# Daughterboard_Power.net
KiCad netlist of a schematic drawn in Altium Designer
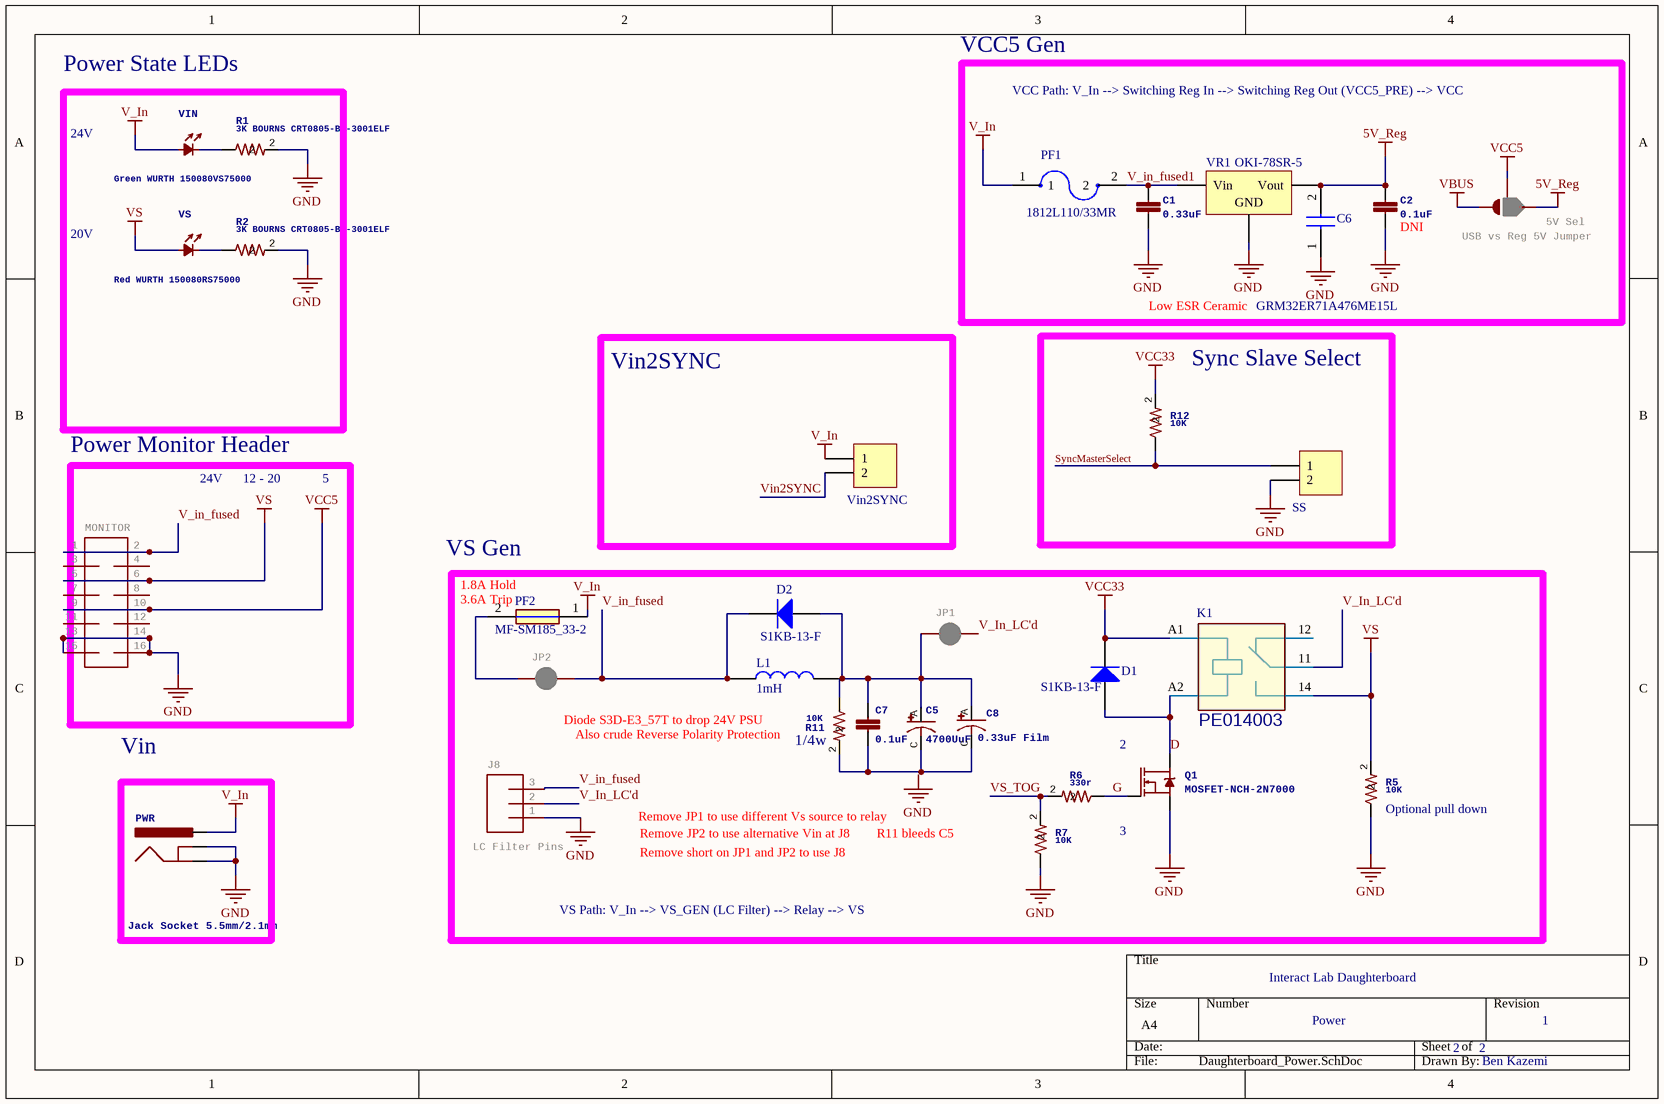
[diagram p0: Daughterboard_Power.SchDoc]

(export (version "E")
  (design (tool "Eeschema 10.0.6"))
  (components
    (comp (ref "5V Sel")
      (value "USB vs Reg 5V Jumper")
      (footprint "SMT-JUMPER_3_1-NC_PASTE_SILK")
      (libsource (lib "SparkFun-Jumpers.Library") (part "JUMPER-SMT_3_1-NC_PASTE_SILK"))
    )
    (comp (ref "C1")
      (value "0.33uF")
      (footprint "CAP0805")
      (libsource (lib "InteractLab") (part "CAP CERAMIC"))
    )
    (comp (ref "C2")
      (value "0.1uF")
      (footprint "CAP0805")
      (libsource (lib "InteractLab") (part "CAP CERAMIC"))
    )
    (comp (ref "C5")
      (value "4700UuF")
      (footprint "CAP-PTH-10MM PITCH 22M")
      (libsource (lib "InteractLab") (part "CAP ELECTRO"))
    )
    (comp (ref "C6")
      (value "GRM32ER71A476ME15L")
      (footprint "SamacSys:CAPC3225X270N")
      (description "Capacitor")
      (fields (field (name "MOUSER PART NUMBER") "81-GRM32ER71A476ME5L"))
      (libsource (lib "*") (part "GRM32ER71A476ME15L"))
    )
    (comp (ref "C7")
      (value "0.1uF")
      (footprint "CAP0805")
      (libsource (lib "InteractLab") (part "CAP CERAMIC"))
    )
    (comp (ref "C8")
      (value "0.33uF Film")
      (footprint "R82DC3330AA60K Film Cap")
      (libsource (lib "InteractLab") (part "CAP ELECTRO"))
    )
    (comp (ref "D1")
      (value "S1KB-13-F")
      (footprint "SMB-DIODE")
      (description "1 Amp General Purpose Rectifier")
      (fields (field (name "PUBLISHER") "Altium Limited"))
      (libsource (lib "InteractLab") (part "Diode SMB"))
    )
    (comp (ref "D2")
      (value "S1KB-13-F")
      (footprint "SMB-DIODE")
      (description "1 Amp General Purpose Rectifier")
      (fields (field (name "PUBLISHER") "Altium Limited"))
      (libsource (lib "InteractLab") (part "Diode SMB"))
    )
    (comp (ref "J8")
      (value "LC Filter Pins")
      (footprint "1X03")
      (libsource (lib "SparkFun-Connectors.Library") (part "CONN_03"))
    )
    (comp (ref "JP1")
      (value "~")
      (footprint "SMT-JUMPER_2_NC_PASTE_SILK")
      (libsource (lib "SparkFun-Jumpers.Library") (part "JUMPER-SMT_2_NC_PASTE_SILK"))
    )
    (comp (ref "JP2")
      (value "~")
      (footprint "SMT-JUMPER_2_NC_PASTE_SILK")
      (libsource (lib "SparkFun-Jumpers.Library") (part "JUMPER-SMT_2_NC_PASTE_SILK"))
    )
    (comp (ref "K1")
      (value "PE014003")
      (footprint "SPDT Power Relay")
      (fields (field (name "MP") "1-1393219-0") (field (name "MF") "TE Connectivity"))
      (libsource (lib "InteractLab") (part "Power Relay SPDT"))
    )
    (comp (ref "L1")
      (value "1mH")
      (footprint "INDUCTOR Hor 2324VRC")
      (description "Bourns 1 mH +/-15% Leaded Inductor, 2.4A Idc, 300m Rdc 2300")
      (fields (field (name "RS PART NUMBER") "1729913") (field (name "MANUFACTURER_PART_NUMBER") "2324-V-RC"))
      (libsource (lib "InteractLab") (part "INDUCTOR 2324-V-RC"))
    )
    (comp (ref "MONITOR")
      (value "Multi connection point. Often used as Generic Header-pin footprint for 0.1 inch spaced/style header connections    You can populate with any combo of single row headers, but if you'd like an exact match, check this:  Header - 2x8 (Male, 0.1\") (PRT-13156)       On any of the 0.1 inch spaced packages, you can populate with these:  Break Away Headers - Straight (PRT-00116)   Break Away Male Headers - Right Angle (PRT-00553)   Female Headers (PRT-00115)   Break Away Headers - Machine Pin (PRT-00117)   Break Away Female Headers - Swiss Machine Pin (PRT-00743)")
      (footprint "2X8_NOSILK")
      (libsource (lib "SparkFun-Connectors.Library") (part "CONN_08X2_NOSILK"))
    )
    (comp (ref "PF1")
      (value "1812L110/33MR")
      (footprint "Polyfuse")
      (description "PTC Resettable Fuse 1.1A_hold_ 1.95A_trip_ 33VDC 20A 0.8W 0.5s 0.06Ohm SMD Solder Pad 1812 T/R")
      (fields (field (name "MF") "Littelfuse Inc."))
      (libsource (lib "InteractLab") (part "1812L110/33MR"))
    )
    (comp (ref "PF2")
      (value "MF-SM185_33-2")
      (footprint "SamacSys:FUSM8867X300N")
      (description "Fuse")
      (fields
        (field (name "MANUFACTURER_PART_NUMBER") "MF-SM185/33-2")
        (field (name "MOUSER PART NUMBER") "652-MF-SM185/33-2")
      )
      (libsource (lib "*") (part "MF-SM185_33-2"))
    )
    (comp (ref "PWR")
      (value "Jack Socket 5.5mm/2.1mm")
      (footprint "POWER_JACK_PTH_LOCK")
      (libsource (lib "InteractLab") (part "POWER_JACKPTH_LOCK"))
    )
    (comp (ref "Q1")
      (value "MOSFET-NCH-2N7000")
      (footprint "TO-92")
      (libsource (lib "InteractLab") (part "MOSFET-NCH-2N7000"))
    )
    (comp (ref "R1")
      (value "3K BOURNS CRT0805-BY-3001ELF")
      (footprint "RES-0805")
      (fields (field (name "MF") "Vishay") (field (name "MPN") "CRCW0603470RFKEA"))
      (libsource (lib "InteractLab") (part "RESISTOR"))
    )
    (comp (ref "R2")
      (value "3K BOURNS CRT0805-BY-3001ELF")
      (footprint "RES-0805")
      (fields (field (name "MF") "Vishay") (field (name "MPN") "CRCW0603470RFKEA"))
      (libsource (lib "InteractLab") (part "RESISTOR"))
    )
    (comp (ref "R5")
      (value "10K")
      (footprint "RES-0805")
      (fields (field (name "MF") "Vishay") (field (name "MPN") "CRCW0603470RFKEA"))
      (libsource (lib "InteractLab") (part "RESISTOR"))
    )
    (comp (ref "R6")
      (value "330r")
      (footprint "RES-0805")
      (fields (field (name "MF") "Vishay") (field (name "MPN") "CRCW0603470RFKEA"))
      (libsource (lib "InteractLab") (part "RESISTOR"))
    )
    (comp (ref "R7")
      (value "10K")
      (footprint "RES-0805")
      (fields (field (name "MF") "Vishay") (field (name "MPN") "CRCW0603470RFKEA"))
      (libsource (lib "InteractLab") (part "RESISTOR"))
    )
    (comp (ref "R11")
      (value "10K")
      (footprint "RES-0805")
      (fields (field (name "MF") "Vishay") (field (name "MPN") "CRCW0603470RFKEA"))
      (libsource (lib "InteractLab") (part "RESISTOR"))
    )
    (comp (ref "R12")
      (value "10K")
      (footprint "RES-0805")
      (fields (field (name "MF") "Vishay") (field (name "MPN") "CRCW0603470RFKEA"))
      (libsource (lib "InteractLab") (part "RESISTOR"))
    )
    (comp (ref "SS")
      (value "~")
      (footprint "HDR1X2")
      (description "Header, 2-Pin")
      (fields (field (name "PUBLISHER") "Altium Limited"))
      (libsource (lib "Miscellaneous Connectors") (part "Header 2"))
    )
    (comp (ref "VIN")
      (value "Green WURTH 150080VS75000")
      (footprint "LED-0805 - GREEN")
      (libsource (lib "InteractLab") (part "LED"))
    )
    (comp (ref "Vin2SYNC")
      (value "~")
      (footprint "HDR1X2")
      (description "Header, 2-Pin")
      (fields (field (name "PUBLISHER") "Altium Limited"))
      (libsource (lib "Miscellaneous Connectors") (part "Header 2"))
    )
    (comp (ref "VR1")
      (value "OKI-78SR-5")
      (footprint "OOKA-78SR")
      (description "Voltage Regulator")
      (fields (field (name "PUBLISHER") "Altium Limited"))
      (libsource (lib "InteractLab") (part "Volt Reg"))
    )
    (comp (ref "VS")
      (value "Red WURTH 150080RS75000")
      (footprint "LED-0805 - RED")
      (libsource (lib "InteractLab") (part "LED"))
    )
  )
  (nets
    (net (code "1") (name "/D") (class "Default")
      (node (ref "D1") (pin "A") (pinfunction "A_A") (pintype "passive"))
      (node (ref "K1") (pin "A2") (pinfunction "A2_A2") (pintype "passive"))
      (node (ref "Q1") (pin "3") (pinfunction "D_3") (pintype "passive"))
    )
    (net (code "2") (name "/G") (class "Default")
      (node (ref "Q1") (pin "2") (pinfunction "G_2") (pintype "passive"))
      (node (ref "R6") (pin "1") (pinfunction "1_1") (pintype "passive"))
    )
    (net (code "3") (name "/SyncMasterSelect") (class "Default")
      (node (ref "R12") (pin "1") (pinfunction "1_1") (pintype "passive"))
      (node (ref "SS") (pin "1") (pinfunction "1_1") (pintype "passive"))
    )
    (net (code "4") (name "/VS_TOG") (class "Default")
      (node (ref "R6") (pin "2") (pinfunction "2_2") (pintype "passive"))
      (node (ref "R7") (pin "2") (pinfunction "2_2") (pintype "passive"))
    )
    (net (code "5") (name "/V_In_LC'd") (class "Default")
      (node (ref "J8") (pin "2") (pinfunction "2_2") (pintype "passive"))
      (node (ref "JP1") (pin "2") (pinfunction "2_2") (pintype "passive"))
      (node (ref "K1") (pin "11") (pinfunction "11_11") (pintype "passive"))
    )
    (net (code "6") (name "/V_in_fused") (class "Default")
      (node (ref "D2") (pin "C") (pinfunction "C_C") (pintype "passive"))
      (node (ref "J8") (pin "3") (pinfunction "3_3") (pintype "passive"))
      (node (ref "JP2") (pin "2") (pinfunction "2_2") (pintype "passive"))
      (node (ref "L1") (pin "1") (pinfunction "1_1") (pintype "passive"))
      (node (ref "MONITOR") (pin "1") (pinfunction "1_1") (pintype "passive"))
      (node (ref "MONITOR") (pin "2") (pinfunction "2_2") (pintype "passive"))
    )
    (net (code "7") (name "/V_in_fused1") (class "Default")
      (node (ref "C1") (pin "1") (pinfunction "1_1") (pintype "passive"))
      (node (ref "PF1") (pin "2") (pinfunction "2_2") (pintype "passive"))
      (node (ref "VR1") (pin "IN") (pinfunction "Vin_IN") (pintype "passive"))
    )
    (net (code "8") (name "/Vin2SYNC") (class "Default")
      (node (ref "Vin2SYNC") (pin "2") (pinfunction "2_2") (pintype "passive"))
    )
    (net (code "9") (name "5V_Reg") (class "Default")
      (node (ref "5V Sel") (pin "3") (pinfunction "3_3") (pintype "passive"))
      (node (ref "C2") (pin "1") (pinfunction "1_1") (pintype "passive"))
      (node (ref "C6") (pin "2") (pinfunction "2_2") (pintype "passive"))
      (node (ref "VR1") (pin "OUT") (pinfunction "Vout_OUT") (pintype "passive"))
    )
    (net (code "10") (name "GND") (class "Default")
      (node (ref "C1") (pin "2") (pinfunction "2_2") (pintype "passive"))
      (node (ref "C2") (pin "2") (pinfunction "2_2") (pintype "passive"))
      (node (ref "C6") (pin "1") (pinfunction "1_1") (pintype "passive"))
      (node (ref "J8") (pin "1") (pinfunction "1_1") (pintype "passive"))
      (node (ref "MONITOR") (pin "13") (pinfunction "13_13") (pintype "passive"))
      (node (ref "MONITOR") (pin "14") (pinfunction "14_14") (pintype "passive"))
      (node (ref "MONITOR") (pin "15") (pinfunction "15_15") (pintype "passive"))
      (node (ref "MONITOR") (pin "16") (pinfunction "16_16") (pintype "passive"))
      (node (ref "PWR") (pin "GND") (pinfunction "GND_GND") (pintype "passive"))
      (node (ref "PWR") (pin "GNDBREAK") (pinfunction "GNDBREAK_GNDBREAK") (pintype "passive"))
      (node (ref "Q1") (pin "1") (pinfunction "S_1") (pintype "passive"))
      (node (ref "R1") (pin "2") (pinfunction "2_2") (pintype "passive"))
      (node (ref "R2") (pin "2") (pinfunction "2_2") (pintype "passive"))
      (node (ref "R5") (pin "1") (pinfunction "1_1") (pintype "passive"))
      (node (ref "R7") (pin "1") (pinfunction "1_1") (pintype "passive"))
      (node (ref "SS") (pin "2") (pinfunction "2_2") (pintype "passive"))
      (node (ref "VR1") (pin "GND") (pinfunction "GND_GND") (pintype "passive"))
    )
    (net (code "11") (name "Net-(C5-PadA)") (class "Default")
      (node (ref "C5") (pin "A") (pinfunction "A_A") (pintype "passive"))
      (node (ref "C7") (pin "1") (pinfunction "1_1") (pintype "passive"))
      (node (ref "C8") (pin "A") (pinfunction "A_A") (pintype "passive"))
      (node (ref "D2") (pin "A") (pinfunction "A_A") (pintype "passive"))
      (node (ref "JP1") (pin "1") (pinfunction "1_1") (pintype "passive"))
      (node (ref "L1") (pin "2") (pinfunction "2_2") (pintype "passive"))
      (node (ref "R11") (pin "1") (pinfunction "1_1") (pintype "passive"))
    )
    (net (code "12") (name "Net-(C5-PadC)") (class "Default")
      (node (ref "C5") (pin "C") (pinfunction "C_C") (pintype "passive"))
      (node (ref "C7") (pin "2") (pinfunction "2_2") (pintype "passive"))
      (node (ref "C8") (pin "C") (pinfunction "C_C") (pintype "passive"))
      (node (ref "R11") (pin "2") (pinfunction "2_2") (pintype "passive"))
    )
    (net (code "13") (name "Net-(JP2-Pad1)") (class "Default")
      (node (ref "JP2") (pin "1") (pinfunction "1_1") (pintype "passive"))
      (node (ref "PF2") (pin "2") (pinfunction "2_2") (pintype "passive"))
    )
    (net (code "14") (name "Net-(R1-Pad1)") (class "Default")
      (node (ref "R1") (pin "1") (pinfunction "1_1") (pintype "passive"))
      (node (ref "VIN") (pin "-") (pinfunction "-_-") (pintype "passive"))
    )
    (net (code "15") (name "Net-(R2-Pad1)") (class "Default")
      (node (ref "R2") (pin "1") (pinfunction "1_1") (pintype "passive"))
      (node (ref "VS") (pin "-") (pinfunction "-_-") (pintype "passive"))
    )
    (net (code "16") (name "VBUS") (class "Default")
      (node (ref "5V Sel") (pin "1") (pinfunction "1_1") (pintype "passive"))
    )
    (net (code "17") (name "VCC5") (class "Default")
      (node (ref "5V Sel") (pin "2") (pinfunction "2_2") (pintype "passive"))
      (node (ref "MONITOR") (pin "10") (pinfunction "10_10") (pintype "passive"))
      (node (ref "MONITOR") (pin "9") (pinfunction "9_9") (pintype "passive"))
    )
    (net (code "18") (name "VCC33") (class "Default")
      (node (ref "D1") (pin "C") (pinfunction "C_C") (pintype "passive"))
      (node (ref "K1") (pin "A1") (pinfunction "A1_A1") (pintype "passive"))
      (node (ref "R12") (pin "2") (pinfunction "2_2") (pintype "passive"))
    )
    (net (code "19") (name "VS") (class "Default")
      (node (ref "K1") (pin "14") (pinfunction "14_14") (pintype "passive"))
      (node (ref "MONITOR") (pin "5") (pinfunction "5_5") (pintype "passive"))
      (node (ref "MONITOR") (pin "6") (pinfunction "6_6") (pintype "passive"))
      (node (ref "R5") (pin "2") (pinfunction "2_2") (pintype "passive"))
      (node (ref "VS") (pin "+") (pinfunction "+_+") (pintype "passive"))
    )
    (net (code "20") (name "V_In") (class "Default")
      (node (ref "PF1") (pin "1") (pinfunction "1_1") (pintype "passive"))
      (node (ref "PF2") (pin "1") (pinfunction "1_1") (pintype "passive"))
      (node (ref "PWR") (pin "PWR") (pinfunction "PWR_PWR") (pintype "passive"))
      (node (ref "VIN") (pin "+") (pinfunction "+_+") (pintype "passive"))
      (node (ref "Vin2SYNC") (pin "1") (pinfunction "1_1") (pintype "passive"))
    )
    (net (code "21") (name "unconnected-(K1-Pad12)") (class "Default")
      (node (ref "K1") (pin "12") (pinfunction "12_12") (pintype "passive"))
    )
    (net (code "22") (name "unconnected-(MONITOR-Pad3)") (class "Default")
      (node (ref "MONITOR") (pin "3") (pinfunction "3_3") (pintype "passive"))
    )
    (net (code "23") (name "unconnected-(MONITOR-Pad4)") (class "Default")
      (node (ref "MONITOR") (pin "4") (pinfunction "4_4") (pintype "passive"))
    )
    (net (code "24") (name "unconnected-(MONITOR-Pad7)") (class "Default")
      (node (ref "MONITOR") (pin "7") (pinfunction "7_7") (pintype "passive"))
    )
    (net (code "25") (name "unconnected-(MONITOR-Pad8)") (class "Default")
      (node (ref "MONITOR") (pin "8") (pinfunction "8_8") (pintype "passive"))
    )
    (net (code "26") (name "unconnected-(MONITOR-Pad11)") (class "Default")
      (node (ref "MONITOR") (pin "11") (pinfunction "11_11") (pintype "passive"))
    )
    (net (code "27") (name "unconnected-(MONITOR-Pad12)") (class "Default")
      (node (ref "MONITOR") (pin "12") (pinfunction "12_12") (pintype "passive"))
    )
  )
)
